# B_OTL_PSU_Board_REV_A.net
KiCad netlist of a schematic drawn in EAGLE
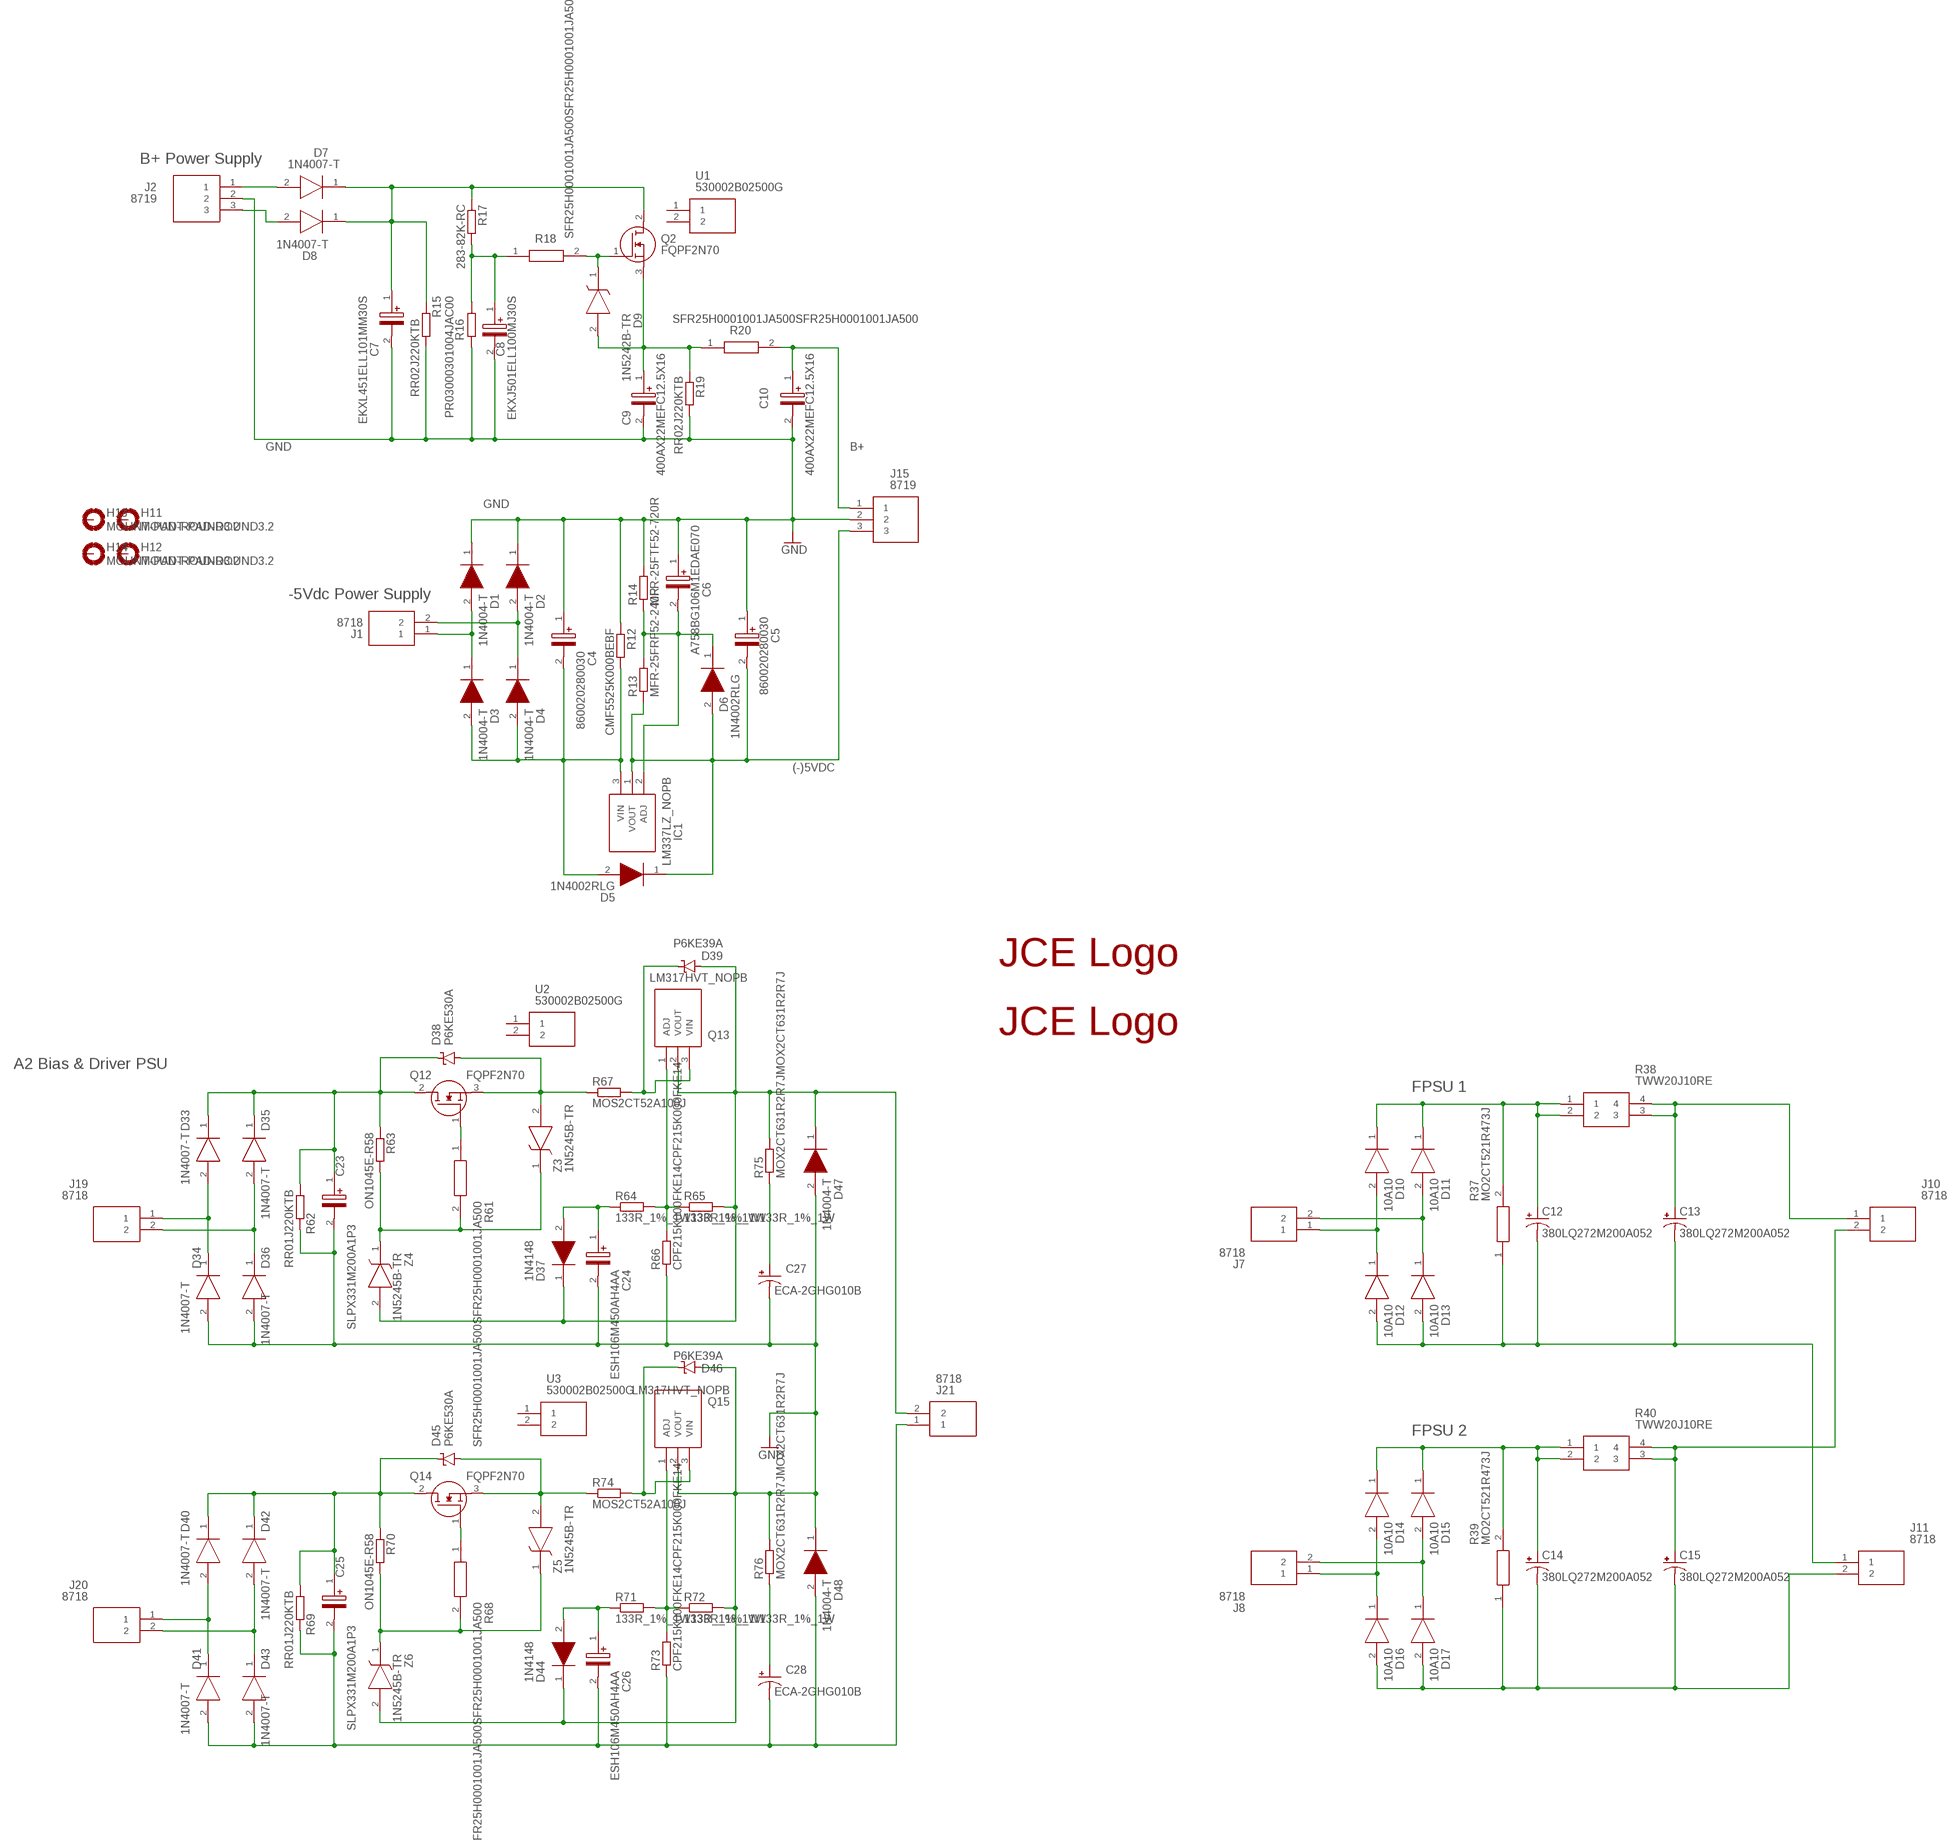
[diagram p0: schematic, sheet 1]

(export (version "E")
  (design (tool "Eeschema 10.0.6"))
  (components
    (comp (ref "C4")
      (value "860020280030")
      (footprint "eagle-import:CAPPRD750W82D1600H3550")
      (libsource (lib "eagle-import") (part "860020280030"))
    )
    (comp (ref "C5")
      (value "860020280030")
      (footprint "eagle-import:CAPPRD750W82D1600H3550")
      (libsource (lib "eagle-import") (part "860020280030"))
    )
    (comp (ref "C6")
      (value "A758BG106M1EDAE070")
      (footprint "eagle-import:CAPPRD200W55D500H800")
      (fields (field (name "MOUSER_PART_NUMBER") "80-A758BG106M1EDAE70"))
      (libsource (lib "eagle-import") (part "A758BG106M1EDAE070"))
    )
    (comp (ref "C7")
      (value "EKXL451ELL101MM30S")
      (footprint "eagle-import:CAPPRD750W80D1825H3200")
      (fields (field (name "MOUSER_PART_NUMBER") "661-EKXL451ELL101MM3"))
      (libsource (lib "eagle-import") (part "EKXL451ELL101MM30S"))
    )
    (comp (ref "C8")
      (value "EKXJ501ELL100MJ30S")
      (footprint "eagle-import:CAPPRD500W60D1025H3150")
      (fields (field (name "MOUSER_PART_NUMBER") "661-EKXJ501ELL100MJ3"))
      (libsource (lib "eagle-import") (part "EKXJ501ELL100MJ30S"))
    )
    (comp (ref "C9")
      (value "400AX22MEFC12.5X16")
      (footprint "eagle-import:CAPPRD500W60D1250H1600")
      (fields (field (name "MOUSER_PART_NUMBER") "232-400AX22MEFC125X1"))
      (libsource (lib "eagle-import") (part "400AX22MEFC12.5X16"))
    )
    (comp (ref "C10")
      (value "400AX22MEFC12.5X16")
      (footprint "eagle-import:CAPPRD500W60D1250H1600")
      (fields (field (name "MOUSER_PART_NUMBER") "232-400AX22MEFC125X1"))
      (libsource (lib "eagle-import") (part "400AX22MEFC12.5X16"))
    )
    (comp (ref "C12")
      (value "380LQ272M200A052")
      (footprint "eagle-import:CAPPRD1000W210D3550H5200")
      (fields (field (name "MOUSER_PART_NUMBER") "5985-380-200V272"))
      (libsource (lib "eagle-import") (part "380LQ272M200A052"))
    )
    (comp (ref "C13")
      (value "380LQ272M200A052")
      (footprint "eagle-import:CAPPRD1000W210D3550H5200")
      (fields (field (name "MOUSER_PART_NUMBER") "5985-380-200V272"))
      (libsource (lib "eagle-import") (part "380LQ272M200A052"))
    )
    (comp (ref "C14")
      (value "380LQ272M200A052")
      (footprint "eagle-import:CAPPRD1000W210D3550H5200")
      (fields (field (name "MOUSER_PART_NUMBER") "5985-380-200V272"))
      (libsource (lib "eagle-import") (part "380LQ272M200A052"))
    )
    (comp (ref "C15")
      (value "380LQ272M200A052")
      (footprint "eagle-import:CAPPRD1000W210D3550H5200")
      (fields (field (name "MOUSER_PART_NUMBER") "5985-380-200V272"))
      (libsource (lib "eagle-import") (part "380LQ272M200A052"))
    )
    (comp (ref "C23")
      (value "SLPX331M200A1P3")
      (footprint "eagle-import:CAPPRD1000W190D2250H2700")
      (libsource (lib "eagle-import") (part "SLPX331M200A1P3"))
    )
    (comp (ref "C24")
      (value "ESH106M450AH4AA")
      (footprint "eagle-import:CAPPRD500W60D1000H2200")
      (libsource (lib "eagle-import") (part "ESH106M450AH4AA"))
    )
    (comp (ref "C25")
      (value "SLPX331M200A1P3")
      (footprint "eagle-import:CAPPRD1000W190D2250H2700")
      (libsource (lib "eagle-import") (part "SLPX331M200A1P3"))
    )
    (comp (ref "C26")
      (value "ESH106M450AH4AA")
      (footprint "eagle-import:CAPPRD500W60D1000H2200")
      (libsource (lib "eagle-import") (part "ESH106M450AH4AA"))
    )
    (comp (ref "C27")
      (value "ECA-2GHG010B")
      (footprint "eagle-import:CAPPRD500W60D630H1120B")
      (libsource (lib "eagle-import") (part "ECA-2GHG010B"))
    )
    (comp (ref "C28")
      (value "ECA-2GHG010B")
      (footprint "eagle-import:CAPPRD500W60D630H1120B")
      (libsource (lib "eagle-import") (part "ECA-2GHG010B"))
    )
    (comp (ref "D1")
      (value "1N4004-T")
      (footprint "eagle-import:DIOAD1408W86L464D236")
      (fields (field (name "MOUSER_PART_NUMBER") "621-1N4004"))
      (libsource (lib "eagle-import") (part "1N4004-T"))
    )
    (comp (ref "D2")
      (value "1N4004-T")
      (footprint "eagle-import:DIOAD1408W86L464D236")
      (fields (field (name "MOUSER_PART_NUMBER") "621-1N4004"))
      (libsource (lib "eagle-import") (part "1N4004-T"))
    )
    (comp (ref "D3")
      (value "1N4004-T")
      (footprint "eagle-import:DIOAD1408W86L464D236")
      (fields (field (name "MOUSER_PART_NUMBER") "621-1N4004"))
      (libsource (lib "eagle-import") (part "1N4004-T"))
    )
    (comp (ref "D4")
      (value "1N4004-T")
      (footprint "eagle-import:DIOAD1408W86L464D236")
      (fields (field (name "MOUSER_PART_NUMBER") "621-1N4004"))
      (libsource (lib "eagle-import") (part "1N4004-T"))
    )
    (comp (ref "D5")
      (value "1N4002RLG")
      (footprint "eagle-import:DIOAD1138W86L465D235B")
      (libsource (lib "eagle-import") (part "1N4002RLG"))
    )
    (comp (ref "D6")
      (value "1N4002RLG")
      (footprint "eagle-import:DIOAD1138W86L465D235B")
      (libsource (lib "eagle-import") (part "1N4002RLG"))
    )
    (comp (ref "D7")
      (value "1N4007-T")
      (footprint "eagle-import:DIOAD1408W86L464D236")
      (fields (field (name "MOUSER_PART_NUMBER") "621-1N4007"))
      (libsource (lib "eagle-import") (part "1N4007-T"))
    )
    (comp (ref "D8")
      (value "1N4007-T")
      (footprint "eagle-import:DIOAD1408W86L464D236")
      (fields (field (name "MOUSER_PART_NUMBER") "621-1N4007"))
      (libsource (lib "eagle-import") (part "1N4007-T"))
    )
    (comp (ref "D9")
      (value "1N5242B-TR")
      (footprint "eagle-import:DIOAD700W55L350D160B")
      (libsource (lib "eagle-import") (part "1N5242B-TR"))
    )
    (comp (ref "D10")
      (value "10A10")
      (footprint "eagle-import:DIOAD1910W130L885D885B")
      (libsource (lib "eagle-import") (part "10A10"))
    )
    (comp (ref "D11")
      (value "10A10")
      (footprint "eagle-import:DIOAD1910W130L885D885B")
      (libsource (lib "eagle-import") (part "10A10"))
    )
    (comp (ref "D12")
      (value "10A10")
      (footprint "eagle-import:DIOAD1910W130L885D885B")
      (libsource (lib "eagle-import") (part "10A10"))
    )
    (comp (ref "D13")
      (value "10A10")
      (footprint "eagle-import:DIOAD1910W130L885D885B")
      (libsource (lib "eagle-import") (part "10A10"))
    )
    (comp (ref "D14")
      (value "10A10")
      (footprint "eagle-import:DIOAD1910W130L885D885B")
      (libsource (lib "eagle-import") (part "10A10"))
    )
    (comp (ref "D15")
      (value "10A10")
      (footprint "eagle-import:DIOAD1910W130L885D885B")
      (libsource (lib "eagle-import") (part "10A10"))
    )
    (comp (ref "D16")
      (value "10A10")
      (footprint "eagle-import:DIOAD1910W130L885D885B")
      (libsource (lib "eagle-import") (part "10A10"))
    )
    (comp (ref "D17")
      (value "10A10")
      (footprint "eagle-import:DIOAD1910W130L885D885B")
      (libsource (lib "eagle-import") (part "10A10"))
    )
    (comp (ref "D33")
      (value "1N4007-T")
      (footprint "eagle-import:DIOAD1408W86L464D236")
      (fields (field (name "MOUSER_PART_NUMBER") "621-1N4007"))
      (libsource (lib "eagle-import") (part "1N4007-T"))
    )
    (comp (ref "D34")
      (value "1N4007-T")
      (footprint "eagle-import:DIOAD1408W86L464D236")
      (fields (field (name "MOUSER_PART_NUMBER") "621-1N4007"))
      (libsource (lib "eagle-import") (part "1N4007-T"))
    )
    (comp (ref "D35")
      (value "1N4007-T")
      (footprint "eagle-import:DIOAD1408W86L464D236")
      (fields (field (name "MOUSER_PART_NUMBER") "621-1N4007"))
      (libsource (lib "eagle-import") (part "1N4007-T"))
    )
    (comp (ref "D36")
      (value "1N4007-T")
      (footprint "eagle-import:DIOAD1408W86L464D236")
      (fields (field (name "MOUSER_PART_NUMBER") "621-1N4007"))
      (libsource (lib "eagle-import") (part "1N4007-T"))
    )
    (comp (ref "D37")
      (value "1N4148")
      (footprint "eagle-import:DIOAD1068W53L380D172")
      (fields (field (name "MOUSER_PART_NUMBER") "512-1N4148"))
      (libsource (lib "eagle-import") (part "1N4148"))
    )
    (comp (ref "D38")
      (value "P6KE530A")
      (footprint "eagle-import:DIOAD1378W86L670D310B")
      (libsource (lib "eagle-import") (part "P6KE530A"))
    )
    (comp (ref "D39")
      (value "P6KE39A")
      (footprint "eagle-import:DIOAD1299W88L640D324B")
      (libsource (lib "eagle-import") (part "P6KE39A"))
    )
    (comp (ref "D40")
      (value "1N4007-T")
      (footprint "eagle-import:DIOAD1408W86L464D236")
      (fields (field (name "MOUSER_PART_NUMBER") "621-1N4007"))
      (libsource (lib "eagle-import") (part "1N4007-T"))
    )
    (comp (ref "D41")
      (value "1N4007-T")
      (footprint "eagle-import:DIOAD1408W86L464D236")
      (fields (field (name "MOUSER_PART_NUMBER") "621-1N4007"))
      (libsource (lib "eagle-import") (part "1N4007-T"))
    )
    (comp (ref "D42")
      (value "1N4007-T")
      (footprint "eagle-import:DIOAD1408W86L464D236")
      (fields (field (name "MOUSER_PART_NUMBER") "621-1N4007"))
      (libsource (lib "eagle-import") (part "1N4007-T"))
    )
    (comp (ref "D43")
      (value "1N4007-T")
      (footprint "eagle-import:DIOAD1408W86L464D236")
      (fields (field (name "MOUSER_PART_NUMBER") "621-1N4007"))
      (libsource (lib "eagle-import") (part "1N4007-T"))
    )
    (comp (ref "D44")
      (value "1N4148")
      (footprint "eagle-import:DIOAD1068W53L380D172")
      (fields (field (name "MOUSER_PART_NUMBER") "512-1N4148"))
      (libsource (lib "eagle-import") (part "1N4148"))
    )
    (comp (ref "D45")
      (value "P6KE530A")
      (footprint "eagle-import:DIOAD1378W86L670D310B")
      (libsource (lib "eagle-import") (part "P6KE530A"))
    )
    (comp (ref "D46")
      (value "P6KE39A")
      (footprint "eagle-import:DIOAD1299W88L640D324B")
      (libsource (lib "eagle-import") (part "P6KE39A"))
    )
    (comp (ref "D47")
      (value "1N4004-T")
      (footprint "eagle-import:DIOAD1408W86L464D236")
      (fields (field (name "MOUSER_PART_NUMBER") "621-1N4004"))
      (libsource (lib "eagle-import") (part "1N4004-T"))
    )
    (comp (ref "D48")
      (value "1N4004-T")
      (footprint "eagle-import:DIOAD1408W86L464D236")
      (fields (field (name "MOUSER_PART_NUMBER") "621-1N4004"))
      (libsource (lib "eagle-import") (part "1N4004-T"))
    )
    (comp (ref "H11")
      (value "MOUNT-PAD-ROUND3.2")
      (footprint "eagle-import:3,2-PAD")
      (libsource (lib "eagle-import") (part "MOUNT-PAD-ROUND3.2"))
    )
    (comp (ref "H12")
      (value "MOUNT-PAD-ROUND3.2")
      (footprint "eagle-import:3,2-PAD")
      (libsource (lib "eagle-import") (part "MOUNT-PAD-ROUND3.2"))
    )
    (comp (ref "H13")
      (value "MOUNT-PAD-ROUND3.2")
      (footprint "eagle-import:3,2-PAD")
      (libsource (lib "eagle-import") (part "MOUNT-PAD-ROUND3.2"))
    )
    (comp (ref "H14")
      (value "MOUNT-PAD-ROUND3.2")
      (footprint "eagle-import:3,2-PAD")
      (libsource (lib "eagle-import") (part "MOUNT-PAD-ROUND3.2"))
    )
    (comp (ref "IC1")
      (value "LM337LZ_NOPB")
      (footprint "eagle-import:LM337LZNOPB")
      (fields (field (name "MANUFACTURER_PART_NUMBER") "LM337LZ/NOPB"))
      (libsource (lib "eagle-import") (part "LM337LZ_NOPB"))
    )
    (comp (ref "J1")
      (value "8718")
      (footprint "eagle-import:SHDR2W99P0X500_1X2_1001X762X10")
      (fields (field (name "MOUSER_PART_NUMBER") "534-8718"))
      (libsource (lib "eagle-import") (part "8718"))
    )
    (comp (ref "J2")
      (value "8719")
      (footprint "eagle-import:8719")
      (fields (field (name "MOUSER_PART_NUMBER") "534-8719"))
      (libsource (lib "eagle-import") (part "8719"))
    )
    (comp (ref "J7")
      (value "8718")
      (footprint "eagle-import:SHDR2W99P0X500_1X2_1001X762X10")
      (fields (field (name "MOUSER_PART_NUMBER") "534-8718"))
      (libsource (lib "eagle-import") (part "8718"))
    )
    (comp (ref "J8")
      (value "8718")
      (footprint "eagle-import:SHDR2W99P0X500_1X2_1001X762X10")
      (fields (field (name "MOUSER_PART_NUMBER") "534-8718"))
      (libsource (lib "eagle-import") (part "8718"))
    )
    (comp (ref "J10")
      (value "8718")
      (footprint "eagle-import:SHDR2W99P0X500_1X2_1001X762X10")
      (fields (field (name "MOUSER_PART_NUMBER") "534-8718"))
      (libsource (lib "eagle-import") (part "8718"))
    )
    (comp (ref "J11")
      (value "8718")
      (footprint "eagle-import:SHDR2W99P0X500_1X2_1001X762X10")
      (fields (field (name "MOUSER_PART_NUMBER") "534-8718"))
      (libsource (lib "eagle-import") (part "8718"))
    )
    (comp (ref "J15")
      (value "8719")
      (footprint "eagle-import:8719")
      (fields (field (name "MOUSER_PART_NUMBER") "534-8719"))
      (libsource (lib "eagle-import") (part "8719"))
    )
    (comp (ref "J19")
      (value "8718")
      (footprint "eagle-import:SHDR2W99P0X500_1X2_1001X762X10")
      (fields (field (name "MOUSER_PART_NUMBER") "534-8718"))
      (libsource (lib "eagle-import") (part "8718"))
    )
    (comp (ref "J20")
      (value "8718")
      (footprint "eagle-import:SHDR2W99P0X500_1X2_1001X762X10")
      (fields (field (name "MOUSER_PART_NUMBER") "534-8718"))
      (libsource (lib "eagle-import") (part "8718"))
    )
    (comp (ref "J21")
      (value "8718")
      (footprint "eagle-import:SHDR2W99P0X500_1X2_1001X762X10")
      (fields (field (name "MOUSER_PART_NUMBER") "534-8718"))
      (libsource (lib "eagle-import") (part "8718"))
    )
    (comp (ref "Q2")
      (value "FQPF2N70")
      (footprint "eagle-import:TO254P490X1016X1977-3P")
      (libsource (lib "eagle-import") (part "FQPF2N70"))
    )
    (comp (ref "Q12")
      (value "FQPF2N70")
      (footprint "eagle-import:TO254P490X1016X1977-3P")
      (libsource (lib "eagle-import") (part "FQPF2N70"))
    )
    (comp (ref "Q13")
      (value "LM317HVT_NOPB")
      (footprint "eagle-import:TO254P470X1028X1955-3P")
      (fields
        (field (name "MANUFACTURER_PART_NUMBER") "LM317HVT/NOPB")
        (field (name "MOUSER_PART_NUMBER") "926-LM317HVT/NOPB")
      )
      (libsource (lib "eagle-import") (part "LM317HVT_NOPB"))
    )
    (comp (ref "Q14")
      (value "FQPF2N70")
      (footprint "eagle-import:TO254P490X1016X1977-3P")
      (libsource (lib "eagle-import") (part "FQPF2N70"))
    )
    (comp (ref "Q15")
      (value "LM317HVT_NOPB")
      (footprint "eagle-import:TO254P470X1028X1955-3P")
      (fields
        (field (name "MANUFACTURER_PART_NUMBER") "LM317HVT/NOPB")
        (field (name "MOUSER_PART_NUMBER") "926-LM317HVT/NOPB")
      )
      (libsource (lib "eagle-import") (part "LM317HVT_NOPB"))
    )
    (comp (ref "R12")
      (value "CMF5525K000BEBF")
      (footprint "eagle-import:RESAD999W69L610D229B")
      (libsource (lib "eagle-import") (part "CMF5525K000BEBF"))
    )
    (comp (ref "R13")
      (value "MFR-25FRF52-240R")
      (footprint "eagle-import:RESAD1000W60L630D230B")
      (libsource (lib "eagle-import") (part "MFR-25FRF52-240R"))
    )
    (comp (ref "R14")
      (value "MFR-25FTF52-720R")
      (footprint "eagle-import:RESAD1000W60L630D230B")
      (libsource (lib "eagle-import") (part "MFR-25FTF52-720R"))
    )
    (comp (ref "R15")
      (value "RR02J220KTB")
      (footprint "eagle-import:RESAD1630W90L900D350B")
      (libsource (lib "eagle-import") (part "RR02J220KTB"))
    )
    (comp (ref "R16")
      (value "PR03000301004JAC00")
      (footprint "eagle-import:RESAD2276W63L1950D520B")
      (libsource (lib "eagle-import") (part "PR03000301004JAC00"))
    )
    (comp (ref "R17")
      (value "283-82K-RC")
      (footprint "eagle-import:RESAD1950W75L1600D550B")
      (libsource (lib "eagle-import") (part "283-82K-RC"))
    )
    (comp (ref "R18")
      (value "SFR25H0001001JA500SFR25H0001001JA500")
      (footprint "eagle-import:RESAD1076W63L700D250B")
      (libsource (lib "eagle-import") (part "SFR25H0001001JA500SFR25H0001001JA500"))
    )
    (comp (ref "R19")
      (value "RR02J220KTB")
      (footprint "eagle-import:RESAD1630W90L900D350B")
      (libsource (lib "eagle-import") (part "RR02J220KTB"))
    )
    (comp (ref "R20")
      (value "SFR25H0001001JA500SFR25H0001001JA500")
      (footprint "eagle-import:RESAD1076W63L700D250B")
      (libsource (lib "eagle-import") (part "SFR25H0001001JA500SFR25H0001001JA500"))
    )
    (comp (ref "R37")
      (value "MO2CT521R473J")
      (footprint "eagle-import:RESAD3950W80L1550D600")
      (libsource (lib "eagle-import") (part "MO2CT521R473J"))
    )
    (comp (ref "R38")
      (value "TWW20J10RE")
      (footprint "eagle-import:TWW20J10RE")
      (fields (field (name "MOUSER_PART_NUMBER") "588-TWW20J10RE"))
      (libsource (lib "eagle-import") (part "TWW20J10RE"))
    )
    (comp (ref "R39")
      (value "MO2CT521R473J")
      (footprint "eagle-import:RESAD3950W80L1550D600")
      (libsource (lib "eagle-import") (part "MO2CT521R473J"))
    )
    (comp (ref "R40")
      (value "TWW20J10RE")
      (footprint "eagle-import:TWW20J10RE")
      (fields (field (name "MOUSER_PART_NUMBER") "588-TWW20J10RE"))
      (libsource (lib "eagle-import") (part "TWW20J10RE"))
    )
    (comp (ref "R61")
      (value "SFR25H0001001JA500SFR25H0001001JA500")
      (footprint "eagle-import:RESAD1076W63L700D250B")
      (libsource (lib "eagle-import") (part "SFR25H0001001JA500SFR25H0001001JA500"))
    )
    (comp (ref "R62")
      (value "RR01J220KTB")
      (footprint "eagle-import:RESAD1110W65L680D260B")
      (libsource (lib "eagle-import") (part "RR01J220KTB"))
    )
    (comp (ref "R63")
      (value "ON1045E-R58")
      (footprint "eagle-import:ON1045E-R58")
      (libsource (lib "eagle-import") (part "ON1045E-R58"))
    )
    (comp (ref "R64")
      (value "133R_1%_1W133R_1%_1W")
      (footprint "eagle-import:RESAD1560W50L1230D250B")
      (libsource (lib "eagle-import") (part "133R_1%_1W133R_1%_1W"))
    )
    (comp (ref "R65")
      (value "133R_1%_1W133R_1%_1W")
      (footprint "eagle-import:RESAD1560W50L1230D250B")
      (libsource (lib "eagle-import") (part "133R_1%_1W133R_1%_1W"))
    )
    (comp (ref "R66")
      (value "CPF215K000FKE14CPF215K000FKE14")
      (footprint "eagle-import:RESAD1683W81L1080D368B")
      (libsource (lib "eagle-import") (part "CPF215K000FKE14CPF215K000FKE14"))
    )
    (comp (ref "R67")
      (value "MOS2CT52A100J")
      (footprint "eagle-import:RESAD1660W80L1200D400B")
      (libsource (lib "eagle-import") (part "MOS2CT52A100J"))
    )
    (comp (ref "R68")
      (value "SFR25H0001001JA500SFR25H0001001JA500")
      (footprint "eagle-import:RESAD1076W63L700D250B")
      (libsource (lib "eagle-import") (part "SFR25H0001001JA500SFR25H0001001JA500"))
    )
    (comp (ref "R69")
      (value "RR01J220KTB")
      (footprint "eagle-import:RESAD1110W65L680D260B")
      (libsource (lib "eagle-import") (part "RR01J220KTB"))
    )
    (comp (ref "R70")
      (value "ON1045E-R58")
      (footprint "eagle-import:ON1045E-R58")
      (libsource (lib "eagle-import") (part "ON1045E-R58"))
    )
    (comp (ref "R71")
      (value "133R_1%_1W133R_1%_1W")
      (footprint "eagle-import:RESAD1560W50L1230D250B")
      (libsource (lib "eagle-import") (part "133R_1%_1W133R_1%_1W"))
    )
    (comp (ref "R72")
      (value "133R_1%_1W133R_1%_1W")
      (footprint "eagle-import:RESAD1560W50L1230D250B")
      (libsource (lib "eagle-import") (part "133R_1%_1W133R_1%_1W"))
    )
    (comp (ref "R73")
      (value "CPF215K000FKE14CPF215K000FKE14")
      (footprint "eagle-import:RESAD1683W81L1080D368B")
      (libsource (lib "eagle-import") (part "CPF215K000FKE14CPF215K000FKE14"))
    )
    (comp (ref "R74")
      (value "MOS2CT52A100J")
      (footprint "eagle-import:RESAD1660W80L1200D400B")
      (libsource (lib "eagle-import") (part "MOS2CT52A100J"))
    )
    (comp (ref "R75")
      (value "MOX2CT631R2R7JMOX2CT631R2R7J")
      (footprint "eagle-import:RESAD2010W80L1550D650B")
      (libsource (lib "eagle-import") (part "MOX2CT631R2R7JMOX2CT631R2R7J"))
    )
    (comp (ref "R76")
      (value "MOX2CT631R2R7JMOX2CT631R2R7J")
      (footprint "eagle-import:RESAD2010W80L1550D650B")
      (libsource (lib "eagle-import") (part "MOX2CT631R2R7JMOX2CT631R2R7J"))
    )
    (comp (ref "SYM1")
      (value "JCE_SMALLSMALL")
      (footprint "eagle-import:JCE_SMALL")
      (libsource (lib "eagle-import") (part "JCE_SMALLSMALL"))
    )
    (comp (ref "SYM2")
      (value "JCE")
      (footprint "eagle-import:JCE")
      (libsource (lib "eagle-import") (part "JCE"))
    )
    (comp (ref "U1")
      (value "530002B02500G")
      (footprint "eagle-import:529802B02500G")
      (fields (field (name "MOUSER_PART_NUMBER") "532-530002B02500G"))
      (libsource (lib "eagle-import") (part "530002B02500G"))
    )
    (comp (ref "U2")
      (value "530002B02500G")
      (footprint "eagle-import:529802B02500G")
      (fields (field (name "MOUSER_PART_NUMBER") "532-530002B02500G"))
      (libsource (lib "eagle-import") (part "530002B02500G"))
    )
    (comp (ref "U3")
      (value "530002B02500G")
      (footprint "eagle-import:529802B02500G")
      (fields (field (name "MOUSER_PART_NUMBER") "532-530002B02500G"))
      (libsource (lib "eagle-import") (part "530002B02500G"))
    )
    (comp (ref "Z3")
      (value "1N5245B-TR")
      (footprint "eagle-import:DIOAD990W55L350D160")
      (fields (field (name "MOUSER_PART_NUMBER") "78-1N5245B"))
      (libsource (lib "eagle-import") (part "1N5245B-TR"))
    )
    (comp (ref "Z4")
      (value "1N5245B-TR")
      (footprint "eagle-import:DIOAD990W55L350D160")
      (fields (field (name "MOUSER_PART_NUMBER") "78-1N5245B"))
      (libsource (lib "eagle-import") (part "1N5245B-TR"))
    )
    (comp (ref "Z5")
      (value "1N5245B-TR")
      (footprint "eagle-import:DIOAD990W55L350D160")
      (fields (field (name "MOUSER_PART_NUMBER") "78-1N5245B"))
      (libsource (lib "eagle-import") (part "1N5245B-TR"))
    )
    (comp (ref "Z6")
      (value "1N5245B-TR")
      (footprint "eagle-import:DIOAD990W55L350D160")
      (fields (field (name "MOUSER_PART_NUMBER") "78-1N5245B"))
      (libsource (lib "eagle-import") (part "1N5245B-TR"))
    )
  )
  (nets
    (net (code "1") (name "/(-)5VDC") (class "Default")
      (node (ref "C5") (pin "2") (pinfunction "-_2") (pintype "bidirectional"))
      (node (ref "D5") (pin "1") (pinfunction "K_1") (pintype "bidirectional"))
      (node (ref "D6") (pin "2") (pinfunction "A_2") (pintype "bidirectional"))
      (node (ref "IC1") (pin "1") (pinfunction "VOUT_1") (pintype "bidirectional"))
      (node (ref "J15") (pin "3") (pinfunction "3_3") (pintype "bidirectional"))
      (node (ref "R13") (pin "1") (pinfunction "1_1") (pintype "passive"))
    )
    (net (code "2") (name "/B+") (class "Default")
      (node (ref "C10") (pin "1") (pinfunction "+_1") (pintype "power_in"))
      (node (ref "J15") (pin "1") (pinfunction "1_1") (pintype "bidirectional"))
      (node (ref "R20") (pin "2") (pinfunction "2_2") (pintype "bidirectional"))
    )
    (net (code "3") (name "GND") (class "Default")
      (node (ref "C10") (pin "2") (pinfunction "-_2") (pintype "power_in"))
      (node (ref "C23") (pin "2") (pinfunction "-_2") (pintype "bidirectional"))
      (node (ref "C24") (pin "2") (pinfunction "-_2") (pintype "bidirectional"))
      (node (ref "C27") (pin "2") (pinfunction "-_2") (pintype "passive"))
      (node (ref "C4") (pin "1") (pinfunction "+_1") (pintype "bidirectional"))
      (node (ref "C5") (pin "1") (pinfunction "+_1") (pintype "bidirectional"))
      (node (ref "C6") (pin "1") (pinfunction "+_1") (pintype "bidirectional"))
      (node (ref "C7") (pin "2") (pinfunction "-_2") (pintype "bidirectional"))
      (node (ref "C8") (pin "2") (pinfunction "-_2") (pintype "bidirectional"))
      (node (ref "C9") (pin "2") (pinfunction "-_2") (pintype "power_in"))
      (node (ref "D1") (pin "1") (pinfunction "K_1") (pintype "bidirectional"))
      (node (ref "D2") (pin "1") (pinfunction "K_1") (pintype "bidirectional"))
      (node (ref "D34") (pin "2") (pinfunction "A_2") (pintype "bidirectional"))
      (node (ref "D36") (pin "2") (pinfunction "A_2") (pintype "bidirectional"))
      (node (ref "D44") (pin "1") (pinfunction "K_1") (pintype "bidirectional"))
      (node (ref "D46") (pin "2") (pinfunction "A_2") (pintype "passive"))
      (node (ref "D47") (pin "2") (pinfunction "A_2") (pintype "bidirectional"))
      (node (ref "D48") (pin "1") (pinfunction "K_1") (pintype "bidirectional"))
      (node (ref "J15") (pin "2") (pinfunction "2_2") (pintype "bidirectional"))
      (node (ref "J2") (pin "2") (pinfunction "2_2") (pintype "bidirectional"))
      (node (ref "Q15") (pin "2") (pinfunction "VOUT_2") (pintype "bidirectional"))
      (node (ref "R12") (pin "1") (pinfunction "1_1") (pintype "passive"))
      (node (ref "R14") (pin "2") (pinfunction "2_2") (pintype "passive"))
      (node (ref "R15") (pin "2") (pinfunction "2_2") (pintype "passive"))
      (node (ref "R16") (pin "2") (pinfunction "2_2") (pintype "passive"))
      (node (ref "R19") (pin "2") (pinfunction "2_2") (pintype "passive"))
      (node (ref "R62") (pin "2") (pinfunction "2_2") (pintype "passive"))
      (node (ref "R66") (pin "1") (pinfunction "1_1") (pintype "passive"))
      (node (ref "R72") (pin "2") (pinfunction "2_2") (pintype "passive"))
      (node (ref "R76") (pin "2") (pinfunction "2_2") (pintype "passive"))
      (node (ref "Z6") (pin "2") (pinfunction "A_2") (pintype "bidirectional"))
    )
    (net (code "4") (name "Net-(C4--)") (class "Default")
      (node (ref "C4") (pin "2") (pinfunction "-_2") (pintype "bidirectional"))
      (node (ref "D3") (pin "2") (pinfunction "A_2") (pintype "bidirectional"))
      (node (ref "D4") (pin "2") (pinfunction "A_2") (pintype "bidirectional"))
      (node (ref "D5") (pin "2") (pinfunction "A_2") (pintype "bidirectional"))
      (node (ref "IC1") (pin "3") (pinfunction "VIN_3") (pintype "bidirectional"))
      (node (ref "R12") (pin "2") (pinfunction "2_2") (pintype "passive"))
    )
    (net (code "5") (name "Net-(C6--)") (class "Default")
      (node (ref "C6") (pin "2") (pinfunction "-_2") (pintype "bidirectional"))
      (node (ref "D6") (pin "1") (pinfunction "K_1") (pintype "bidirectional"))
      (node (ref "IC1") (pin "2") (pinfunction "ADJ_2") (pintype "bidirectional"))
      (node (ref "R13") (pin "2") (pinfunction "2_2") (pintype "passive"))
      (node (ref "R14") (pin "1") (pinfunction "1_1") (pintype "passive"))
    )
    (net (code "6") (name "Net-(C7-+)") (class "Default")
      (node (ref "C7") (pin "1") (pinfunction "+_1") (pintype "bidirectional"))
      (node (ref "D7") (pin "1") (pinfunction "K_1") (pintype "bidirectional"))
      (node (ref "D8") (pin "1") (pinfunction "K_1") (pintype "bidirectional"))
      (node (ref "Q2") (pin "2") (pinfunction "D_2") (pintype "power_in"))
      (node (ref "R15") (pin "1") (pinfunction "1_1") (pintype "passive"))
      (node (ref "R17") (pin "1") (pinfunction "1_1") (pintype "passive"))
    )
    (net (code "7") (name "Net-(C8-+)") (class "Default")
      (node (ref "C8") (pin "1") (pinfunction "+_1") (pintype "bidirectional"))
      (node (ref "R16") (pin "1") (pinfunction "1_1") (pintype "passive"))
      (node (ref "R17") (pin "2") (pinfunction "2_2") (pintype "passive"))
      (node (ref "R18") (pin "1") (pinfunction "1_1") (pintype "bidirectional"))
    )
    (net (code "8") (name "Net-(C9-+)") (class "Default")
      (node (ref "C9") (pin "1") (pinfunction "+_1") (pintype "power_in"))
      (node (ref "D9") (pin "2") (pinfunction "A_2") (pintype "bidirectional"))
      (node (ref "Q2") (pin "3") (pinfunction "S_3") (pintype "power_in"))
      (node (ref "R19") (pin "1") (pinfunction "1_1") (pintype "passive"))
      (node (ref "R20") (pin "1") (pinfunction "1_1") (pintype "bidirectional"))
    )
    (net (code "9") (name "Net-(C12-+)") (class "Default")
      (node (ref "C12") (pin "1") (pinfunction "+_1") (pintype "passive"))
      (node (ref "D10") (pin "1") (pinfunction "K_1") (pintype "bidirectional"))
      (node (ref "D11") (pin "1") (pinfunction "K_1") (pintype "bidirectional"))
      (node (ref "R37") (pin "2") (pinfunction "2_2") (pintype "bidirectional"))
      (node (ref "R38") (pin "1") (pinfunction "1_1") (pintype "bidirectional"))
      (node (ref "R38") (pin "2") (pinfunction "2_2") (pintype "bidirectional"))
    )
    (net (code "10") (name "Net-(C12--)") (class "Default")
      (node (ref "C12") (pin "2") (pinfunction "-_2") (pintype "passive"))
      (node (ref "C13") (pin "2") (pinfunction "-_2") (pintype "passive"))
      (node (ref "D12") (pin "2") (pinfunction "A_2") (pintype "bidirectional"))
      (node (ref "D13") (pin "2") (pinfunction "A_2") (pintype "bidirectional"))
      (node (ref "J11") (pin "1") (pinfunction "1_1") (pintype "bidirectional"))
      (node (ref "R37") (pin "1") (pinfunction "1_1") (pintype "bidirectional"))
    )
    (net (code "11") (name "Net-(C13-+)") (class "Default")
      (node (ref "C13") (pin "1") (pinfunction "+_1") (pintype "passive"))
      (node (ref "J10") (pin "1") (pinfunction "1_1") (pintype "bidirectional"))
      (node (ref "R38") (pin "3") (pinfunction "3_3") (pintype "bidirectional"))
      (node (ref "R38") (pin "4") (pinfunction "4_4") (pintype "bidirectional"))
    )
    (net (code "12") (name "Net-(C14-+)") (class "Default")
      (node (ref "C14") (pin "1") (pinfunction "+_1") (pintype "passive"))
      (node (ref "D14") (pin "1") (pinfunction "K_1") (pintype "bidirectional"))
      (node (ref "D15") (pin "1") (pinfunction "K_1") (pintype "bidirectional"))
      (node (ref "R39") (pin "2") (pinfunction "2_2") (pintype "bidirectional"))
      (node (ref "R40") (pin "1") (pinfunction "1_1") (pintype "bidirectional"))
      (node (ref "R40") (pin "2") (pinfunction "2_2") (pintype "bidirectional"))
    )
    (net (code "13") (name "Net-(C14--)") (class "Default")
      (node (ref "C14") (pin "2") (pinfunction "-_2") (pintype "passive"))
      (node (ref "C15") (pin "2") (pinfunction "-_2") (pintype "passive"))
      (node (ref "D16") (pin "2") (pinfunction "A_2") (pintype "bidirectional"))
      (node (ref "D17") (pin "2") (pinfunction "A_2") (pintype "bidirectional"))
      (node (ref "J11") (pin "2") (pinfunction "2_2") (pintype "bidirectional"))
      (node (ref "R39") (pin "1") (pinfunction "1_1") (pintype "bidirectional"))
    )
    (net (code "14") (name "Net-(C15-+)") (class "Default")
      (node (ref "C15") (pin "1") (pinfunction "+_1") (pintype "passive"))
      (node (ref "J10") (pin "2") (pinfunction "2_2") (pintype "bidirectional"))
      (node (ref "R40") (pin "3") (pinfunction "3_3") (pintype "bidirectional"))
      (node (ref "R40") (pin "4") (pinfunction "4_4") (pintype "bidirectional"))
    )
    (net (code "15") (name "Net-(C23-+)") (class "Default")
      (node (ref "C23") (pin "1") (pinfunction "+_1") (pintype "bidirectional"))
      (node (ref "D33") (pin "1") (pinfunction "K_1") (pintype "bidirectional"))
      (node (ref "D35") (pin "1") (pinfunction "K_1") (pintype "bidirectional"))
      (node (ref "D38") (pin "1") (pinfunction "C_1") (pintype "passive"))
      (node (ref "Q12") (pin "2") (pinfunction "D_2") (pintype "power_in"))
      (node (ref "R62") (pin "1") (pinfunction "1_1") (pintype "passive"))
      (node (ref "R63") (pin "1") (pinfunction "1_1") (pintype "passive"))
    )
    (net (code "16") (name "Net-(C24-+)") (class "Default")
      (node (ref "C24") (pin "1") (pinfunction "+_1") (pintype "bidirectional"))
      (node (ref "D37") (pin "2") (pinfunction "A_2") (pintype "bidirectional"))
      (node (ref "R64") (pin "1") (pinfunction "1_1") (pintype "passive"))
    )
    (net (code "17") (name "Net-(C25-+)") (class "Default")
      (node (ref "C25") (pin "1") (pinfunction "+_1") (pintype "bidirectional"))
      (node (ref "D40") (pin "1") (pinfunction "K_1") (pintype "bidirectional"))
      (node (ref "D42") (pin "1") (pinfunction "K_1") (pintype "bidirectional"))
      (node (ref "D45") (pin "1") (pinfunction "C_1") (pintype "passive"))
      (node (ref "Q14") (pin "2") (pinfunction "D_2") (pintype "power_in"))
      (node (ref "R69") (pin "1") (pinfunction "1_1") (pintype "passive"))
      (node (ref "R70") (pin "1") (pinfunction "1_1") (pintype "passive"))
    )
    (net (code "18") (name "Net-(C25--)") (class "Default")
      (node (ref "C25") (pin "2") (pinfunction "-_2") (pintype "bidirectional"))
      (node (ref "C26") (pin "2") (pinfunction "-_2") (pintype "bidirectional"))
      (node (ref "C28") (pin "2") (pinfunction "-_2") (pintype "passive"))
      (node (ref "D41") (pin "2") (pinfunction "A_2") (pintype "bidirectional"))
      (node (ref "D43") (pin "2") (pinfunction "A_2") (pintype "bidirectional"))
      (node (ref "D48") (pin "2") (pinfunction "A_2") (pintype "bidirectional"))
      (node (ref "J21") (pin "1") (pinfunction "1_1") (pintype "bidirectional"))
      (node (ref "R69") (pin "2") (pinfunction "2_2") (pintype "passive"))
      (node (ref "R73") (pin "1") (pinfunction "1_1") (pintype "passive"))
    )
    (net (code "19") (name "Net-(C26-+)") (class "Default")
      (node (ref "C26") (pin "1") (pinfunction "+_1") (pintype "bidirectional"))
      (node (ref "D44") (pin "2") (pinfunction "A_2") (pintype "bidirectional"))
      (node (ref "R71") (pin "1") (pinfunction "1_1") (pintype "passive"))
    )
    (net (code "20") (name "Net-(C27-+)") (class "Default")
      (node (ref "C27") (pin "1") (pinfunction "+_1") (pintype "passive"))
      (node (ref "R75") (pin "1") (pinfunction "1_1") (pintype "passive"))
    )
    (net (code "21") (name "Net-(C28-+)") (class "Default")
      (node (ref "C28") (pin "1") (pinfunction "+_1") (pintype "passive"))
      (node (ref "R76") (pin "1") (pinfunction "1_1") (pintype "passive"))
    )
    (net (code "22") (name "Net-(D1-A)") (class "Default")
      (node (ref "D1") (pin "2") (pinfunction "A_2") (pintype "bidirectional"))
      (node (ref "D3") (pin "1") (pinfunction "K_1") (pintype "bidirectional"))
      (node (ref "J1") (pin "1") (pinfunction "1_1") (pintype "bidirectional"))
    )
    (net (code "23") (name "Net-(D2-A)") (class "Default")
      (node (ref "D2") (pin "2") (pinfunction "A_2") (pintype "bidirectional"))
      (node (ref "D4") (pin "1") (pinfunction "K_1") (pintype "bidirectional"))
      (node (ref "J1") (pin "2") (pinfunction "2_2") (pintype "bidirectional"))
    )
    (net (code "24") (name "Net-(D7-A)") (class "Default")
      (node (ref "D7") (pin "2") (pinfunction "A_2") (pintype "bidirectional"))
      (node (ref "J2") (pin "1") (pinfunction "1_1") (pintype "bidirectional"))
    )
    (net (code "25") (name "Net-(D8-A)") (class "Default")
      (node (ref "D8") (pin "2") (pinfunction "A_2") (pintype "bidirectional"))
      (node (ref "J2") (pin "3") (pinfunction "3_3") (pintype "bidirectional"))
    )
    (net (code "26") (name "Net-(D9-K)") (class "Default")
      (node (ref "D9") (pin "1") (pinfunction "K_1") (pintype "bidirectional"))
      (node (ref "Q2") (pin "1") (pinfunction "G_1") (pintype "input"))
      (node (ref "R18") (pin "2") (pinfunction "2_2") (pintype "bidirectional"))
    )
    (net (code "27") (name "Net-(D10-A)") (class "Default")
      (node (ref "D10") (pin "2") (pinfunction "A_2") (pintype "bidirectional"))
      (node (ref "D12") (pin "1") (pinfunction "K_1") (pintype "bidirectional"))
      (node (ref "J7") (pin "1") (pinfunction "1_1") (pintype "bidirectional"))
    )
    (net (code "28") (name "Net-(D11-A)") (class "Default")
      (node (ref "D11") (pin "2") (pinfunction "A_2") (pintype "bidirectional"))
      (node (ref "D13") (pin "1") (pinfunction "K_1") (pintype "bidirectional"))
      (node (ref "J7") (pin "2") (pinfunction "2_2") (pintype "bidirectional"))
    )
    (net (code "29") (name "Net-(D14-A)") (class "Default")
      (node (ref "D14") (pin "2") (pinfunction "A_2") (pintype "bidirectional"))
      (node (ref "D16") (pin "1") (pinfunction "K_1") (pintype "bidirectional"))
      (node (ref "J8") (pin "1") (pinfunction "1_1") (pintype "bidirectional"))
    )
    (net (code "30") (name "Net-(D15-A)") (class "Default")
      (node (ref "D15") (pin "2") (pinfunction "A_2") (pintype "bidirectional"))
      (node (ref "D17") (pin "1") (pinfunction "K_1") (pintype "bidirectional"))
      (node (ref "J8") (pin "2") (pinfunction "2_2") (pintype "bidirectional"))
    )
    (net (code "31") (name "Net-(D33-A)") (class "Default")
      (node (ref "D33") (pin "2") (pinfunction "A_2") (pintype "bidirectional"))
      (node (ref "D34") (pin "1") (pinfunction "K_1") (pintype "bidirectional"))
      (node (ref "J19") (pin "1") (pinfunction "1_1") (pintype "bidirectional"))
    )
    (net (code "32") (name "Net-(D35-A)") (class "Default")
      (node (ref "D35") (pin "2") (pinfunction "A_2") (pintype "bidirectional"))
      (node (ref "D36") (pin "1") (pinfunction "K_1") (pintype "bidirectional"))
      (node (ref "J19") (pin "2") (pinfunction "2_2") (pintype "bidirectional"))
    )
    (net (code "33") (name "Net-(D37-K)") (class "Default")
      (node (ref "D37") (pin "1") (pinfunction "K_1") (pintype "bidirectional"))
      (node (ref "D39") (pin "2") (pinfunction "A_2") (pintype "passive"))
      (node (ref "D47") (pin "1") (pinfunction "K_1") (pintype "bidirectional"))
      (node (ref "J21") (pin "2") (pinfunction "2_2") (pintype "bidirectional"))
      (node (ref "Q13") (pin "2") (pinfunction "VOUT_2") (pintype "bidirectional"))
      (node (ref "R65") (pin "2") (pinfunction "2_2") (pintype "passive"))
      (node (ref "R75") (pin "2") (pinfunction "2_2") (pintype "passive"))
      (node (ref "Z4") (pin "2") (pinfunction "A_2") (pintype "bidirectional"))
    )
    (net (code "34") (name "Net-(D38-A)") (class "Default")
      (node (ref "D38") (pin "2") (pinfunction "A_2") (pintype "passive"))
      (node (ref "Q12") (pin "3") (pinfunction "S_3") (pintype "power_in"))
      (node (ref "R67") (pin "1") (pinfunction "1_1") (pintype "passive"))
      (node (ref "Z3") (pin "2") (pinfunction "A_2") (pintype "bidirectional"))
    )
    (net (code "35") (name "Net-(D39-C)") (class "Default")
      (node (ref "D39") (pin "1") (pinfunction "C_1") (pintype "passive"))
      (node (ref "Q13") (pin "3") (pinfunction "VIN_3") (pintype "bidirectional"))
      (node (ref "R67") (pin "2") (pinfunction "2_2") (pintype "passive"))
    )
    (net (code "36") (name "Net-(D40-A)") (class "Default")
      (node (ref "D40") (pin "2") (pinfunction "A_2") (pintype "bidirectional"))
      (node (ref "D41") (pin "1") (pinfunction "K_1") (pintype "bidirectional"))
      (node (ref "J20") (pin "1") (pinfunction "1_1") (pintype "bidirectional"))
    )
    (net (code "37") (name "Net-(D42-A)") (class "Default")
      (node (ref "D42") (pin "2") (pinfunction "A_2") (pintype "bidirectional"))
      (node (ref "D43") (pin "1") (pinfunction "K_1") (pintype "bidirectional"))
      (node (ref "J20") (pin "2") (pinfunction "2_2") (pintype "bidirectional"))
    )
    (net (code "38") (name "Net-(D45-A)") (class "Default")
      (node (ref "D45") (pin "2") (pinfunction "A_2") (pintype "passive"))
      (node (ref "Q14") (pin "3") (pinfunction "S_3") (pintype "power_in"))
      (node (ref "R74") (pin "1") (pinfunction "1_1") (pintype "passive"))
      (node (ref "Z5") (pin "2") (pinfunction "A_2") (pintype "bidirectional"))
    )
    (net (code "39") (name "Net-(D46-C)") (class "Default")
      (node (ref "D46") (pin "1") (pinfunction "C_1") (pintype "passive"))
      (node (ref "Q15") (pin "3") (pinfunction "VIN_3") (pintype "bidirectional"))
      (node (ref "R74") (pin "2") (pinfunction "2_2") (pintype "passive"))
    )
    (net (code "40") (name "Net-(Q12-G)") (class "Default")
      (node (ref "Q12") (pin "1") (pinfunction "G_1") (pintype "input"))
      (node (ref "R61") (pin "1") (pinfunction "1_1") (pintype "bidirectional"))
    )
    (net (code "41") (name "Net-(Q13-ADJ)") (class "Default")
      (node (ref "Q13") (pin "1") (pinfunction "ADJ_1") (pintype "bidirectional"))
      (node (ref "R64") (pin "2") (pinfunction "2_2") (pintype "passive"))
      (node (ref "R65") (pin "1") (pinfunction "1_1") (pintype "passive"))
      (node (ref "R66") (pin "2") (pinfunction "2_2") (pintype "passive"))
    )
    (net (code "42") (name "Net-(Q14-G)") (class "Default")
      (node (ref "Q14") (pin "1") (pinfunction "G_1") (pintype "input"))
      (node (ref "R68") (pin "1") (pinfunction "1_1") (pintype "bidirectional"))
    )
    (net (code "43") (name "Net-(Q15-ADJ)") (class "Default")
      (node (ref "Q15") (pin "1") (pinfunction "ADJ_1") (pintype "bidirectional"))
      (node (ref "R71") (pin "2") (pinfunction "2_2") (pintype "passive"))
      (node (ref "R72") (pin "1") (pinfunction "1_1") (pintype "passive"))
      (node (ref "R73") (pin "2") (pinfunction "2_2") (pintype "passive"))
    )
    (net (code "44") (name "Net-(Z3-K)") (class "Default")
      (node (ref "R61") (pin "2") (pinfunction "2_2") (pintype "bidirectional"))
      (node (ref "R63") (pin "2") (pinfunction "2_2") (pintype "passive"))
      (node (ref "Z3") (pin "1") (pinfunction "K_1") (pintype "bidirectional"))
      (node (ref "Z4") (pin "1") (pinfunction "K_1") (pintype "bidirectional"))
    )
    (net (code "45") (name "Net-(Z5-K)") (class "Default")
      (node (ref "R68") (pin "2") (pinfunction "2_2") (pintype "bidirectional"))
      (node (ref "R70") (pin "2") (pinfunction "2_2") (pintype "passive"))
      (node (ref "Z5") (pin "1") (pinfunction "K_1") (pintype "bidirectional"))
      (node (ref "Z6") (pin "1") (pinfunction "K_1") (pintype "bidirectional"))
    )
    (net (code "46") (name "unconnected-(H11-MOUNT-PadB3,2)") (class "Default")
      (node (ref "H11") (pin "B3,2") (pinfunction "MOUNT_B3,2") (pintype "passive"))
    )
    (net (code "47") (name "unconnected-(H12-MOUNT-PadB3,2)") (class "Default")
      (node (ref "H12") (pin "B3,2") (pinfunction "MOUNT_B3,2") (pintype "passive"))
    )
    (net (code "48") (name "unconnected-(H13-MOUNT-PadB3,2)") (class "Default")
      (node (ref "H13") (pin "B3,2") (pinfunction "MOUNT_B3,2") (pintype "passive"))
    )
    (net (code "49") (name "unconnected-(H14-MOUNT-PadB3,2)") (class "Default")
      (node (ref "H14") (pin "B3,2") (pinfunction "MOUNT_B3,2") (pintype "passive"))
    )
    (net (code "50") (name "unconnected-(U1-Pad1)") (class "Default")
      (node (ref "U1") (pin "1") (pinfunction "1_1") (pintype "bidirectional"))
    )
    (net (code "51") (name "unconnected-(U1-Pad2)") (class "Default")
      (node (ref "U1") (pin "2") (pinfunction "2_2") (pintype "bidirectional"))
    )
    (net (code "52") (name "unconnected-(U2-Pad1)") (class "Default")
      (node (ref "U2") (pin "1") (pinfunction "1_1") (pintype "bidirectional"))
    )
    (net (code "53") (name "unconnected-(U2-Pad2)") (class "Default")
      (node (ref "U2") (pin "2") (pinfunction "2_2") (pintype "bidirectional"))
    )
    (net (code "54") (name "unconnected-(U3-Pad1)") (class "Default")
      (node (ref "U3") (pin "1") (pinfunction "1_1") (pintype "bidirectional"))
    )
    (net (code "55") (name "unconnected-(U3-Pad2)") (class "Default")
      (node (ref "U3") (pin "2") (pinfunction "2_2") (pintype "bidirectional"))
    )
  )
)
